# 1-Schematic_smart-shade.net
KiCad netlist of a schematic drawn in EasyEDA
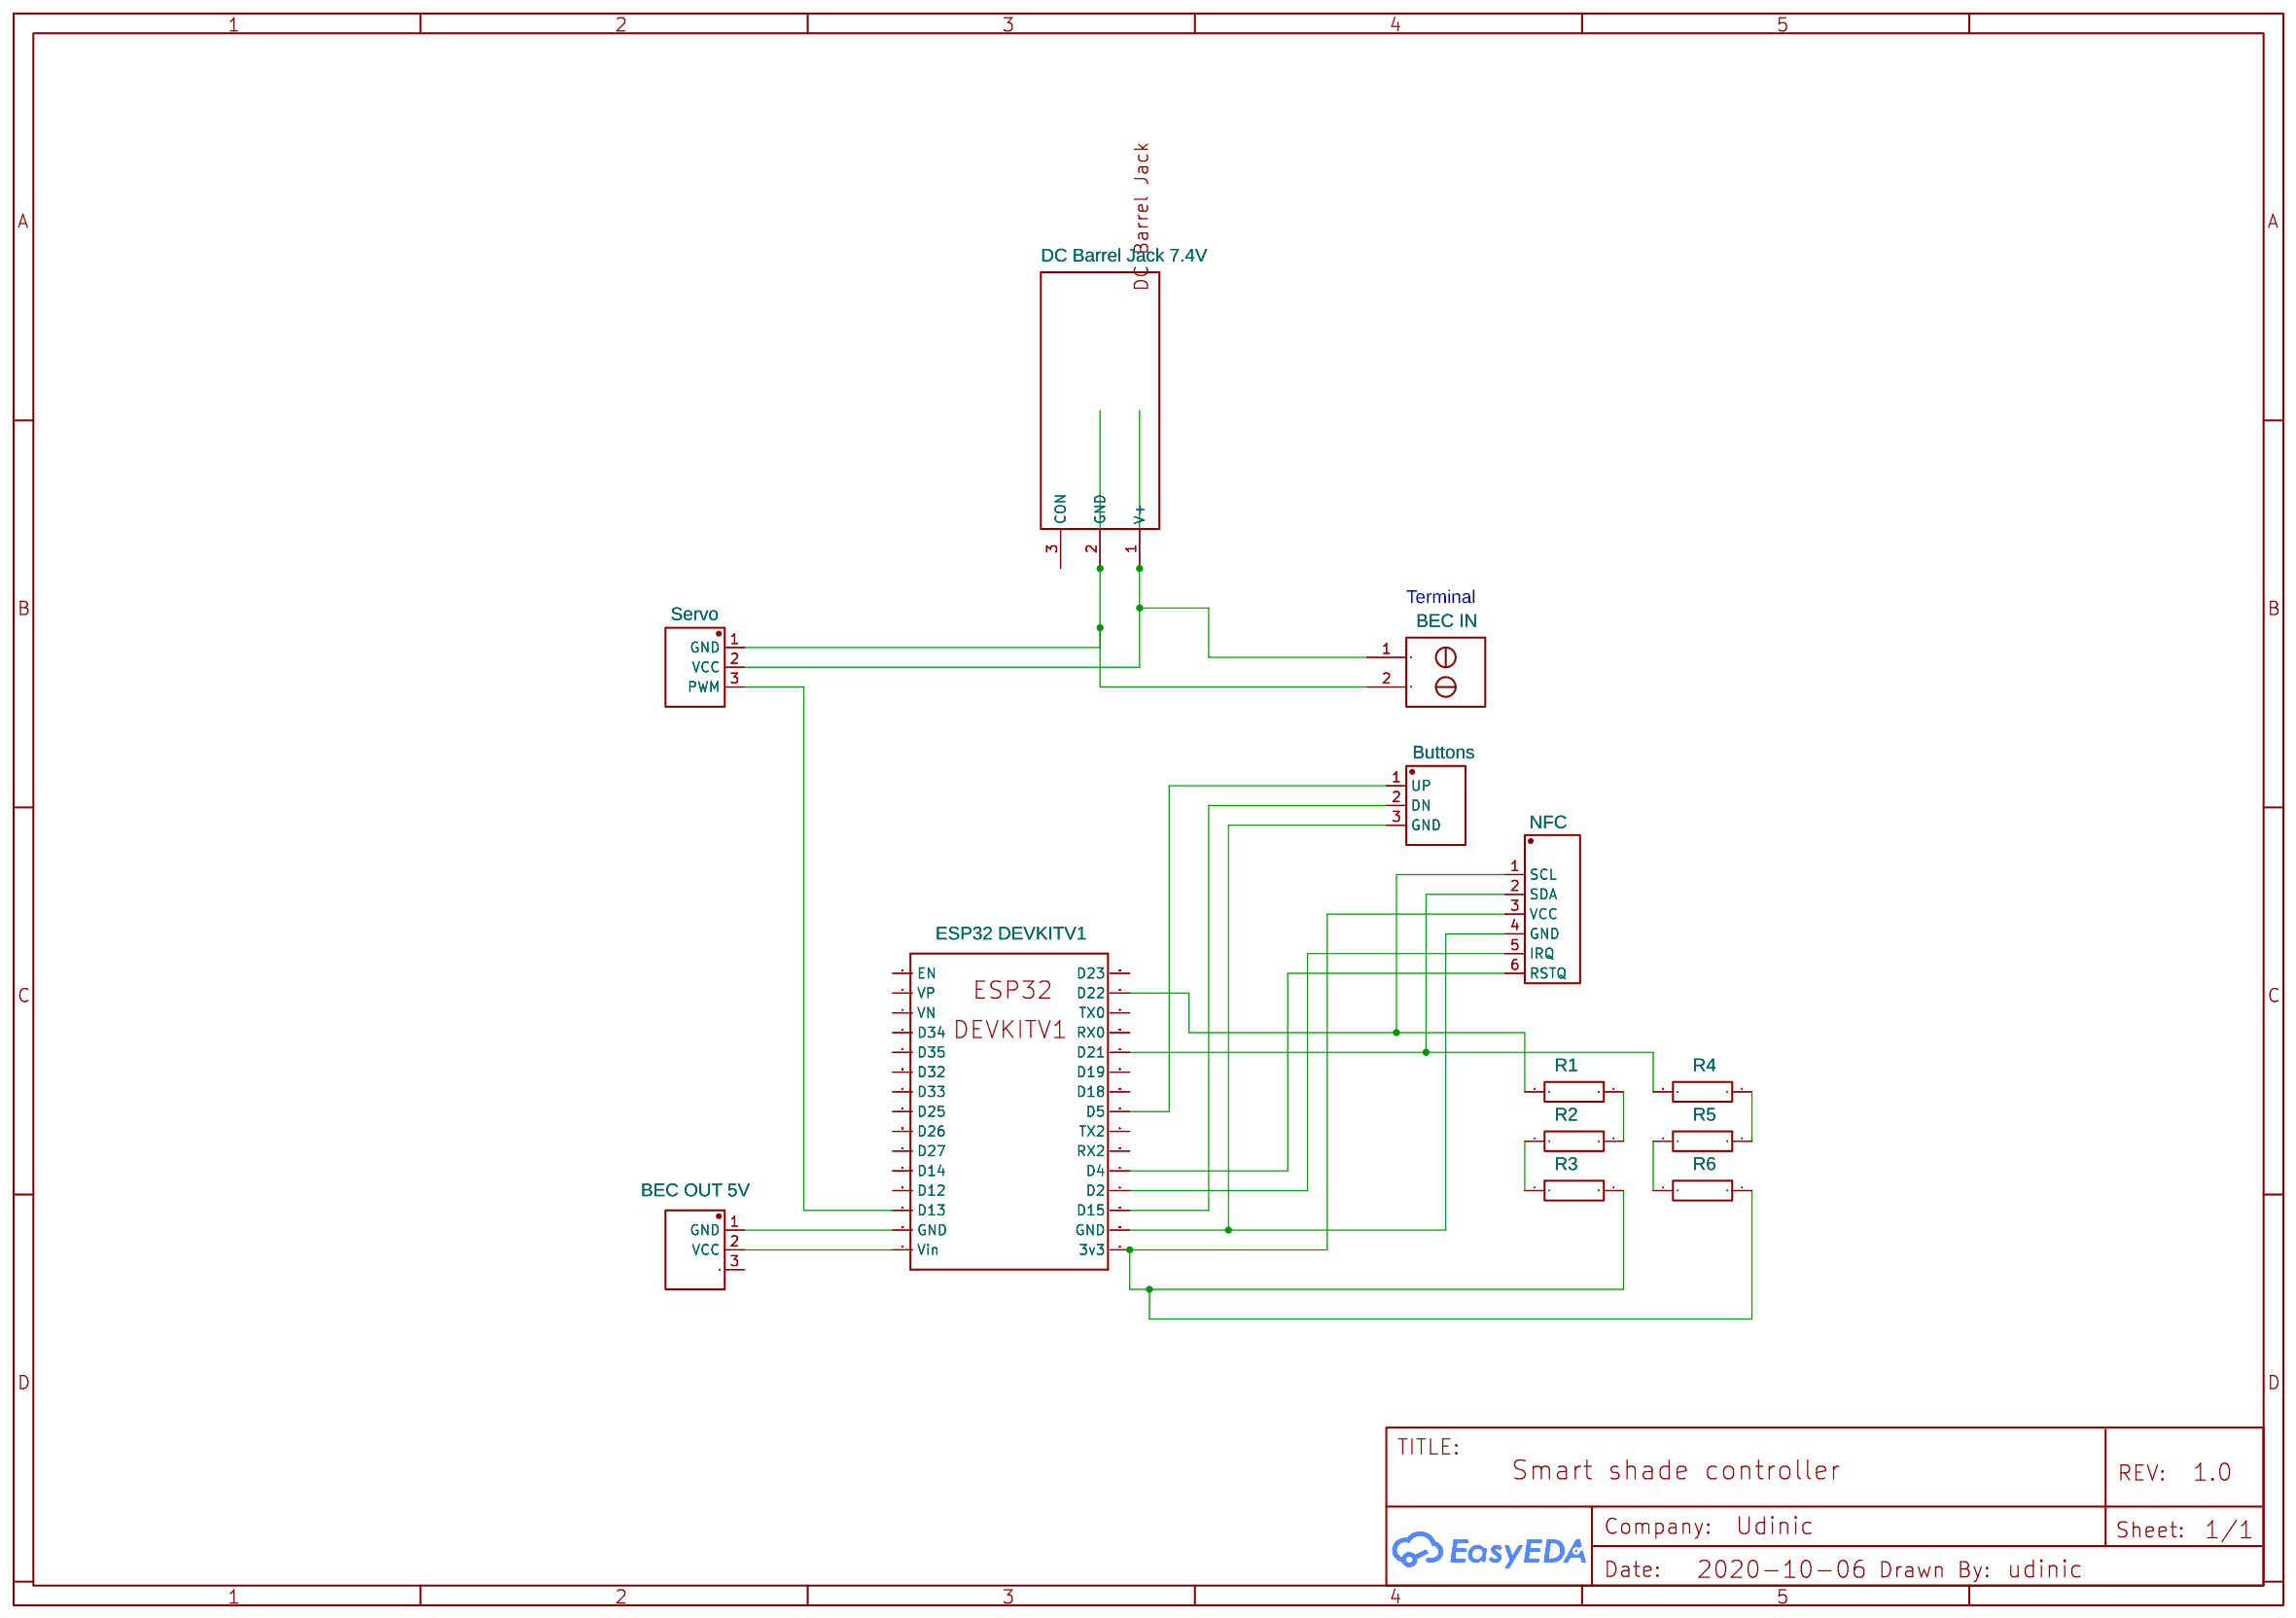
[diagram p0: schematic sheet]

(export (version "E")
  (design (tool "Eeschema 10.0.6"))
  (components
    (comp (ref "BEC-IN")
      (value "BEC IN")
      (fields (field (name "BOM_Manufacturer Part") "Terminal, Screw, 5mm"))
      (libsource (lib "") (part "Terminal, Screw, 5mm"))
    )
    (comp (ref "BEC-OUT")
      (value "BEC OUT 5V")
      (fields
        (field (name "BOM_Manufacturer Part") "Headers  Pins2.54")
        (field (name "BOM_Supplier Part") "C53043")
      )
      (libsource (lib "") (part "HEADERS  PINS2.54 3PINS"))
    )
    (comp (ref "BTNS")
      (value "Buttons")
      (fields
        (field (name "BOM_Manufacturer Part") "Headers  Pins2.54")
        (field (name "BOM_Supplier Part") "C53043")
      )
      (libsource (lib "") (part "HEADERS  PINS2.54 3PINS COPY"))
    )
    (comp (ref "ESP32") (value "ESP32 DEVKITV1") (libsource (lib "") (part "ESP32 DEVKITV1")))
    (comp (ref "NFC")
      (value "NFC")
      (fields
        (field (name "BOM_Manufacturer Part") "Headers  Pins2.54")
        (field (name "BOM_Supplier Part") "C53043")
      )
      (libsource (lib "") (part "Headers_Pins2.54_1x6"))
    )
    (comp (ref "R1") (value "RESISTOR") (libsource (lib "") (part "RESISTOR")))
    (comp (ref "R2") (value "RESISTOR") (libsource (lib "") (part "RESISTOR")))
    (comp (ref "R3") (value "RESISTOR") (libsource (lib "") (part "RESISTOR")))
    (comp (ref "R4") (value "RESISTOR") (libsource (lib "") (part "RESISTOR")))
    (comp (ref "R5") (value "RESISTOR") (libsource (lib "") (part "RESISTOR")))
    (comp (ref "R6") (value "RESISTOR") (libsource (lib "") (part "RESISTOR")))
    (comp (ref "SERVO")
      (value "Servo")
      (fields
        (field (name "BOM_Manufacturer Part") "Headers  Pins2.54")
        (field (name "BOM_Supplier Part") "C53043")
      )
      (libsource (lib "") (part "HEADERS  PINS2.54 3PINS_1"))
    )
    (comp (ref "U2")
      (value "DC Barrel Jack 7.4V")
      (fields
        (field (name "BOM_Manufacturer Part") "DC Barrel Jack 20V 4A")
        (field (name "BOM_Supplier Part") "10811")
      )
      (libsource (lib "") (part "DC Barrel Jack 20V 4A"))
    )
  )
  (nets
    (net (code "1") (name "Net-(BEC-OUT-GND)") (class "Default")
      (node (ref "BEC-OUT") (pin "1") (pinfunction "GND_1") (pintype "unspecified"))
      (node (ref "ESP32") (pin "GND#2") (pinfunction "GND_GND#2") (pintype "bidirectional"))
    )
    (net (code "2") (name "Net-(BEC-OUT-VCC)") (class "Default")
      (node (ref "BEC-OUT") (pin "2") (pinfunction "VCC_2") (pintype "unspecified"))
      (node (ref "ESP32") (pin "Vin") (pinfunction "Vin_Vin") (pintype "bidirectional"))
    )
    (net (code "3") (name "Net-(BTNS-DN)") (class "Default")
      (node (ref "BTNS") (pin "2") (pinfunction "DN_2") (pintype "unspecified"))
      (node (ref "ESP32") (pin "D15") (pinfunction "D15_D15") (pintype "bidirectional"))
    )
    (net (code "4") (name "Net-(BTNS-GND)") (class "Default")
      (node (ref "BTNS") (pin "3") (pinfunction "GND_3") (pintype "unspecified"))
      (node (ref "ESP32") (pin "GND#1") (pinfunction "GND_GND#1") (pintype "bidirectional"))
      (node (ref "NFC") (pin "4") (pinfunction "GND_4") (pintype "unspecified"))
    )
    (net (code "5") (name "Net-(BTNS-UP)") (class "Default")
      (node (ref "BTNS") (pin "1") (pinfunction "UP_1") (pintype "unspecified"))
      (node (ref "ESP32") (pin "D5") (pinfunction "D5_D5") (pintype "bidirectional"))
    )
    (net (code "6") (name "Net-(NFC-IRQ)") (class "Default")
      (node (ref "ESP32") (pin "D2") (pinfunction "D2_D2") (pintype "bidirectional"))
      (node (ref "NFC") (pin "5") (pinfunction "IRQ_5") (pintype "unspecified"))
    )
    (net (code "7") (name "Net-(NFC-RSTQ)") (class "Default")
      (node (ref "ESP32") (pin "D4") (pinfunction "D4_D4") (pintype "bidirectional"))
      (node (ref "NFC") (pin "6") (pinfunction "RSTQ_6") (pintype "unspecified"))
    )
    (net (code "8") (name "Net-(NFC-SCL)") (class "Default")
      (node (ref "ESP32") (pin "D22") (pinfunction "D22_D22") (pintype "bidirectional"))
      (node (ref "NFC") (pin "1") (pinfunction "SCL_1") (pintype "unspecified"))
      (node (ref "R1") (pin "1") (pinfunction "1_1") (pintype "unspecified"))
    )
    (net (code "9") (name "Net-(NFC-SDA)") (class "Default")
      (node (ref "ESP32") (pin "D21") (pinfunction "D21_D21") (pintype "bidirectional"))
      (node (ref "NFC") (pin "2") (pinfunction "SDA_2") (pintype "unspecified"))
      (node (ref "R4") (pin "1") (pinfunction "1_1") (pintype "unspecified"))
    )
    (net (code "10") (name "Net-(NFC-VCC)") (class "Default")
      (node (ref "ESP32") (pin "3v3") (pinfunction "3v3_3v3") (pintype "bidirectional"))
      (node (ref "NFC") (pin "3") (pinfunction "VCC_3") (pintype "unspecified"))
      (node (ref "R3") (pin "2") (pinfunction "2_2") (pintype "unspecified"))
      (node (ref "R6") (pin "2") (pinfunction "2_2") (pintype "unspecified"))
    )
    (net (code "11") (name "Net-(R1-Pad2)") (class "Default")
      (node (ref "R1") (pin "2") (pinfunction "2_2") (pintype "unspecified"))
      (node (ref "R2") (pin "2") (pinfunction "2_2") (pintype "unspecified"))
    )
    (net (code "12") (name "Net-(R2-Pad1)") (class "Default")
      (node (ref "R2") (pin "1") (pinfunction "1_1") (pintype "unspecified"))
      (node (ref "R3") (pin "1") (pinfunction "1_1") (pintype "unspecified"))
    )
    (net (code "13") (name "Net-(R4-Pad2)") (class "Default")
      (node (ref "R4") (pin "2") (pinfunction "2_2") (pintype "unspecified"))
      (node (ref "R5") (pin "2") (pinfunction "2_2") (pintype "unspecified"))
    )
    (net (code "14") (name "Net-(R5-Pad1)") (class "Default")
      (node (ref "R5") (pin "1") (pinfunction "1_1") (pintype "unspecified"))
      (node (ref "R6") (pin "1") (pinfunction "1_1") (pintype "unspecified"))
    )
    (net (code "15") (name "Net-(SERVO-GND)") (class "Default")
      (node (ref "BEC-IN") (pin "2") (pinfunction "2_2") (pintype "unspecified"))
      (node (ref "SERVO") (pin "1") (pinfunction "GND_1") (pintype "unspecified"))
      (node (ref "U2") (pin "2") (pinfunction "GND_2") (pintype "unspecified"))
    )
    (net (code "16") (name "Net-(SERVO-PWM)") (class "Default")
      (node (ref "ESP32") (pin "D13") (pinfunction "D13_D13") (pintype "bidirectional"))
      (node (ref "SERVO") (pin "3") (pinfunction "PWM_3") (pintype "unspecified"))
    )
    (net (code "17") (name "Net-(SERVO-VCC)") (class "Default")
      (node (ref "BEC-IN") (pin "1") (pinfunction "1_1") (pintype "unspecified"))
      (node (ref "SERVO") (pin "2") (pinfunction "VCC_2") (pintype "unspecified"))
      (node (ref "U2") (pin "1") (pinfunction "V+_1") (pintype "unspecified"))
    )
    (net (code "18") (name "unconnected-(BEC-OUT-OFF-Pad3)") (class "Default")
      (node (ref "BEC-OUT") (pin "3") (pinfunction "OFF_3") (pintype "unspecified"))
    )
    (net (code "19") (name "unconnected-(ESP32-PadD12)") (class "Default")
      (node (ref "ESP32") (pin "D12") (pinfunction "D12_D12") (pintype "bidirectional"))
    )
    (net (code "20") (name "unconnected-(ESP32-PadD14)") (class "Default")
      (node (ref "ESP32") (pin "D14") (pinfunction "D14_D14") (pintype "bidirectional"))
    )
    (net (code "21") (name "unconnected-(ESP32-PadD18)") (class "Default")
      (node (ref "ESP32") (pin "D18") (pinfunction "D18_D18") (pintype "bidirectional"))
    )
    (net (code "22") (name "unconnected-(ESP32-PadD19)") (class "Default")
      (node (ref "ESP32") (pin "D19") (pinfunction "D19_D19") (pintype "bidirectional"))
    )
    (net (code "23") (name "unconnected-(ESP32-PadD23)") (class "Default")
      (node (ref "ESP32") (pin "D23") (pinfunction "D23_D23") (pintype "bidirectional"))
    )
    (net (code "24") (name "unconnected-(ESP32-PadD25)") (class "Default")
      (node (ref "ESP32") (pin "D25") (pinfunction "D25_D25") (pintype "bidirectional"))
    )
    (net (code "25") (name "unconnected-(ESP32-PadD26)") (class "Default")
      (node (ref "ESP32") (pin "D26") (pinfunction "D26_D26") (pintype "bidirectional"))
    )
    (net (code "26") (name "unconnected-(ESP32-PadD27)") (class "Default")
      (node (ref "ESP32") (pin "D27") (pinfunction "D27_D27") (pintype "bidirectional"))
    )
    (net (code "27") (name "unconnected-(ESP32-PadD32)") (class "Default")
      (node (ref "ESP32") (pin "D32") (pinfunction "D32_D32") (pintype "bidirectional"))
    )
    (net (code "28") (name "unconnected-(ESP32-PadD33)") (class "Default")
      (node (ref "ESP32") (pin "D33") (pinfunction "D33_D33") (pintype "bidirectional"))
    )
    (net (code "29") (name "unconnected-(ESP32-PadD34)") (class "Default")
      (node (ref "ESP32") (pin "D34") (pinfunction "D34_D34") (pintype "bidirectional"))
    )
    (net (code "30") (name "unconnected-(ESP32-PadD35)") (class "Default")
      (node (ref "ESP32") (pin "D35") (pinfunction "D35_D35") (pintype "bidirectional"))
    )
    (net (code "31") (name "unconnected-(ESP32-PadEN)") (class "Default")
      (node (ref "ESP32") (pin "EN") (pinfunction "EN_EN") (pintype "bidirectional"))
    )
    (net (code "32") (name "unconnected-(ESP32-PadRX0)") (class "Default")
      (node (ref "ESP32") (pin "RX0") (pinfunction "RX0_RX0") (pintype "bidirectional"))
    )
    (net (code "33") (name "unconnected-(ESP32-PadRX2)") (class "Default")
      (node (ref "ESP32") (pin "RX2") (pinfunction "RX2_RX2") (pintype "bidirectional"))
    )
    (net (code "34") (name "unconnected-(ESP32-PadTX0)") (class "Default")
      (node (ref "ESP32") (pin "TX0") (pinfunction "TX0_TX0") (pintype "bidirectional"))
    )
    (net (code "35") (name "unconnected-(ESP32-PadTX2)") (class "Default")
      (node (ref "ESP32") (pin "TX2") (pinfunction "TX2_TX2") (pintype "bidirectional"))
    )
    (net (code "36") (name "unconnected-(ESP32-PadVN)") (class "Default")
      (node (ref "ESP32") (pin "VN") (pinfunction "VN_VN") (pintype "bidirectional"))
    )
    (net (code "37") (name "unconnected-(ESP32-PadVP)") (class "Default")
      (node (ref "ESP32") (pin "VP") (pinfunction "VP_VP") (pintype "bidirectional"))
    )
    (net (code "38") (name "unconnected-(U2-CON-Pad3)") (class "Default")
      (node (ref "U2") (pin "3") (pinfunction "CON_3") (pintype "unspecified"))
    )
  )
)
